# AlarmClock_Schematic.net
KiCad netlist of a schematic drawn in EAGLE
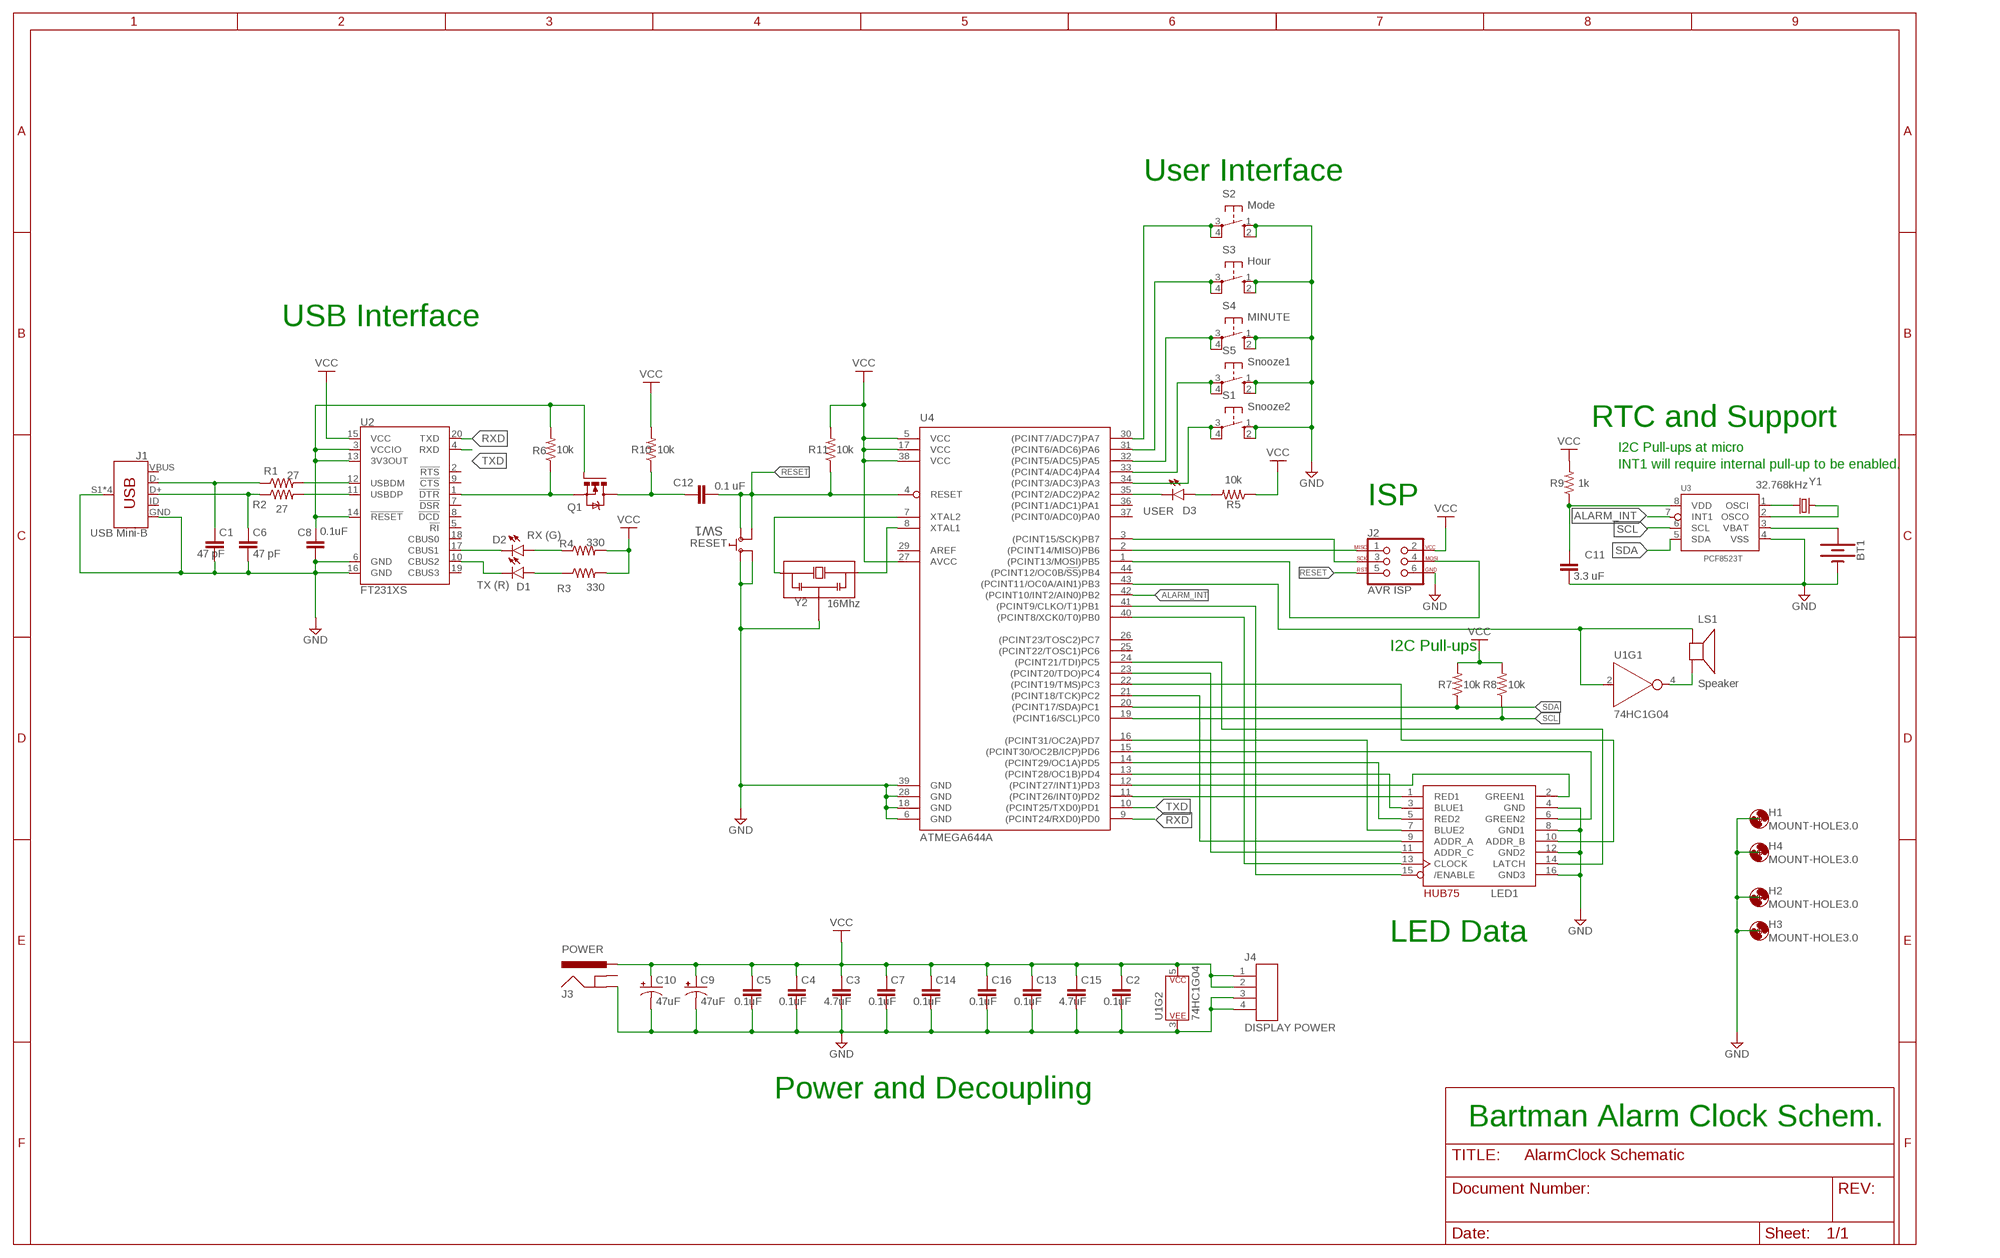
[diagram p0: schematic, sheet 1]

(export (version "E")
  (design (tool "Eeschema 10.0.6"))
  (components
    (comp (ref "BT1")
      (value "BATTERY-20MM_SMD_4LEGS")
      (footprint "eagle-import:BATTCON_20MM_4LEGS")
      (libsource (lib "eagle-import") (part "BATTERY-20MM_SMD_4LEGS"))
    )
    (comp (ref "C1")
      (value "47 pF")
      (footprint "eagle-import:CAPC2012X110")
      (libsource (lib "eagle-import") (part "CCHIP-0805(2012-METRIC)_"))
    )
    (comp (ref "C2")
      (value "0.1uF")
      (footprint "eagle-import:CAPC2012X110")
      (libsource (lib "eagle-import") (part "CCHIP-0805(2012-METRIC)_"))
    )
    (comp (ref "C3")
      (value "4.7uF")
      (footprint "eagle-import:CAPC2012X110")
      (libsource (lib "eagle-import") (part "CCHIP-0805(2012-METRIC)_"))
    )
    (comp (ref "C4")
      (value "0.1uF")
      (footprint "eagle-import:CAPC2012X110")
      (libsource (lib "eagle-import") (part "CCHIP-0805(2012-METRIC)_"))
    )
    (comp (ref "C5")
      (value "0.1uF")
      (footprint "eagle-import:CAPC2012X110")
      (libsource (lib "eagle-import") (part "CCHIP-0805(2012-METRIC)_"))
    )
    (comp (ref "C6")
      (value "47 pF")
      (footprint "eagle-import:CAPC2012X110")
      (libsource (lib "eagle-import") (part "CCHIP-0805(2012-METRIC)_"))
    )
    (comp (ref "C7")
      (value "0.1uF")
      (footprint "eagle-import:CAPC2012X110")
      (libsource (lib "eagle-import") (part "CCHIP-0805(2012-METRIC)_"))
    )
    (comp (ref "C8")
      (value "0.1uF")
      (footprint "eagle-import:CAPC2012X110")
      (libsource (lib "eagle-import") (part "CCHIP-0805(2012-METRIC)_"))
    )
    (comp (ref "C9")
      (value "47uF")
      (footprint "eagle-import:PANASONIC_D")
      (libsource (lib "eagle-import") (part "47UF-POLAR-PANASONIC_D-35V-20%"))
    )
    (comp (ref "C10")
      (value "47uF")
      (footprint "eagle-import:PANASONIC_D")
      (libsource (lib "eagle-import") (part "47UF-POLAR-PANASONIC_D-35V-20%"))
    )
    (comp (ref "C11")
      (value "3.3 uF")
      (footprint "eagle-import:CAPC2012X110")
      (libsource (lib "eagle-import") (part "CCHIP-0805(2012-METRIC)_"))
    )
    (comp (ref "C12")
      (value "0.1 uF")
      (footprint "eagle-import:CAPC2012X110")
      (libsource (lib "eagle-import") (part "CCHIP-0805(2012-METRIC)_"))
    )
    (comp (ref "C13")
      (value "0.1uF")
      (footprint "eagle-import:CAPC2012X110")
      (libsource (lib "eagle-import") (part "CCHIP-0805(2012-METRIC)_"))
    )
    (comp (ref "C14")
      (value "0.1uF")
      (footprint "eagle-import:CAPC2012X110")
      (libsource (lib "eagle-import") (part "CCHIP-0805(2012-METRIC)_"))
    )
    (comp (ref "C15")
      (value "4.7uF")
      (footprint "eagle-import:CAPC2012X110")
      (libsource (lib "eagle-import") (part "CCHIP-0805(2012-METRIC)_"))
    )
    (comp (ref "C16")
      (value "0.1uF")
      (footprint "eagle-import:CAPC2012X110")
      (libsource (lib "eagle-import") (part "CCHIP-0805(2012-METRIC)_"))
    )
    (comp (ref "D1")
      (value "TX (R)")
      (footprint "eagle-import:LEDC2012X110N_R")
      (fields (field (name "COLOR") "RED"))
      (libsource (lib "eagle-import") (part "LED_CHIPRED-2012"))
    )
    (comp (ref "D2")
      (value "RX (G)")
      (footprint "eagle-import:LEDC2012X110N_G")
      (fields (field (name "COLOR") "Green") (field (name "COLOR_1") "RX (G)"))
      (libsource (lib "eagle-import") (part "LED_CHIPGREEN-2012"))
    )
    (comp (ref "D3")
      (value "USER")
      (footprint "eagle-import:LEDC2012X110N_R")
      (fields (field (name "COLOR") "RED"))
      (libsource (lib "eagle-import") (part "LED_CHIPRED-2012"))
    )
    (comp (ref "H1")
      (value "MOUNT-HOLE3.0")
      (footprint "eagle-import:3,0")
      (libsource (lib "eagle-import") (part "MOUNT-HOLE3.0"))
    )
    (comp (ref "H2")
      (value "MOUNT-HOLE3.0")
      (footprint "eagle-import:3,0")
      (libsource (lib "eagle-import") (part "MOUNT-HOLE3.0"))
    )
    (comp (ref "H3")
      (value "MOUNT-HOLE3.0")
      (footprint "eagle-import:3,0")
      (libsource (lib "eagle-import") (part "MOUNT-HOLE3.0"))
    )
    (comp (ref "H4")
      (value "MOUNT-HOLE3.0")
      (footprint "eagle-import:3,0")
      (libsource (lib "eagle-import") (part "MOUNT-HOLE3.0"))
    )
    (comp (ref "J1")
      (value "USB Mini-B")
      (footprint "eagle-import:USB-MINIB")
      (libsource (lib "eagle-import") (part "USB_MINI-B_SMT"))
    )
    (comp (ref "J2")
      (value "AVR ISP")
      (footprint "eagle-import:2X3")
      (libsource (lib "eagle-import") (part "AVR_SPI_PROG_3X2PTH"))
    )
    (comp (ref "J3")
      (value "POWER")
      (footprint "eagle-import:POWER_JACK_PTH_BREAD")
      (libsource (lib "eagle-import") (part "POWER_JACKPTH_BREAD"))
    )
    (comp (ref "J4")
      (value "DISPLAY POWER")
      (footprint "eagle-import:JST_B4P-VH(LF)(SN)")
      (fields (field (name "MANUFACTURER") "JST Sales"))
      (libsource (lib "eagle-import") (part "B4P-VH(LF)(SN)"))
    )
    (comp (ref "LED1")
      (value "HUB75MATRIX")
      (footprint "eagle-import:2X08-IDC")
      (libsource (lib "eagle-import") (part "HUB75MATRIX"))
    )
    (comp (ref "LS1")
      (value "Speaker")
      (footprint "eagle-import:XDCR_CPT-1625-80-SMT-TR")
      (fields
        (field (name "DIGI-KEY_PART_NUMBER") "102-CPT-1625-80-SMT-CT-ND")
        (field (name "MF") "CUI Devices")
        (field (name "MP") "CPT-1625-80-SMT-TR")
      )
      (libsource (lib "eagle-import") (part "CPT-1625-80-SMT-TR"))
    )
    (comp (ref "Q1")
      (value "BSS123")
      (footprint "eagle-import:SOT23")
      (fields (field (name "MANUFACTURER") "ON Semiconductor") (field (name "MPN") "BSS123L"))
      (libsource (lib "eagle-import") (part "NMOSFET_-SOT23BSS123"))
    )
    (comp (ref "R1")
      (value "27")
      (footprint "eagle-import:RESC2012X65")
      (libsource (lib "eagle-import") (part "R-USCHIP-0805(2012-METRIC)_"))
    )
    (comp (ref "R2")
      (value "27")
      (footprint "eagle-import:RESC2012X65")
      (libsource (lib "eagle-import") (part "R-USCHIP-0805(2012-METRIC)_"))
    )
    (comp (ref "R3")
      (value "330")
      (footprint "eagle-import:RESC2012X65")
      (libsource (lib "eagle-import") (part "R-USCHIP-0805(2012-METRIC)_"))
    )
    (comp (ref "R4")
      (value "330")
      (footprint "eagle-import:RESC2012X65")
      (libsource (lib "eagle-import") (part "R-USCHIP-0805(2012-METRIC)_"))
    )
    (comp (ref "R5")
      (value "10k")
      (footprint "eagle-import:RESC2012X65")
      (libsource (lib "eagle-import") (part "R-USCHIP-0805(2012-METRIC)_"))
    )
    (comp (ref "R6")
      (value "10k")
      (footprint "eagle-import:RESC2012X65")
      (libsource (lib "eagle-import") (part "R-USCHIP-0805(2012-METRIC)_"))
    )
    (comp (ref "R7")
      (value "10k")
      (footprint "eagle-import:RESC2012X65")
      (libsource (lib "eagle-import") (part "R-USCHIP-0805(2012-METRIC)_"))
    )
    (comp (ref "R8")
      (value "10k")
      (footprint "eagle-import:RESC2012X65")
      (libsource (lib "eagle-import") (part "R-USCHIP-0805(2012-METRIC)_"))
    )
    (comp (ref "R9")
      (value "1k")
      (footprint "eagle-import:RESC2012X65")
      (libsource (lib "eagle-import") (part "R-USCHIP-0805(2012-METRIC)_"))
    )
    (comp (ref "R10")
      (value "10k")
      (footprint "eagle-import:RESC2012X65")
      (libsource (lib "eagle-import") (part "R-USCHIP-0805(2012-METRIC)_"))
    )
    (comp (ref "R11")
      (value "10k")
      (footprint "eagle-import:RESC2012X65")
      (libsource (lib "eagle-import") (part "R-USCHIP-0805(2012-METRIC)_"))
    )
    (comp (ref "S1")
      (value "Snooze2")
      (footprint "eagle-import:B3F-10XX")
      (fields
        (field (name "DIGI-KEY_PART_NUMBER") "39-B3F-1052-G-ND")
        (field (name "MF") "Omron")
        (field (name "MP") "B3F-1052")
      )
      (libsource (lib "eagle-import") (part "B3F-1052"))
    )
    (comp (ref "S2")
      (value "Mode")
      (footprint "eagle-import:B3F-10XX")
      (fields
        (field (name "DIGI-KEY_PART_NUMBER") "39-B3F-1052-G-ND")
        (field (name "MF") "Omron")
        (field (name "MP") "B3F-1052")
      )
      (libsource (lib "eagle-import") (part "B3F-1052"))
    )
    (comp (ref "S3")
      (value "Hour")
      (footprint "eagle-import:B3F-10XX")
      (fields
        (field (name "DIGI-KEY_PART_NUMBER") "39-B3F-1052-G-ND")
        (field (name "MF") "Omron")
        (field (name "MP") "B3F-1052")
      )
      (libsource (lib "eagle-import") (part "B3F-1052"))
    )
    (comp (ref "S4")
      (value "MINUTE")
      (footprint "eagle-import:B3F-10XX")
      (fields
        (field (name "DIGI-KEY_PART_NUMBER") "39-B3F-1052-G-ND")
        (field (name "MF") "Omron")
        (field (name "MP") "B3F-1052")
      )
      (libsource (lib "eagle-import") (part "B3F-1052"))
    )
    (comp (ref "S5")
      (value "Snooze1")
      (footprint "eagle-import:B3F-10XX")
      (fields
        (field (name "DIGI-KEY_PART_NUMBER") "39-B3F-1052-G-ND")
        (field (name "MF") "Omron")
        (field (name "MP") "B3F-1052")
      )
      (libsource (lib "eagle-import") (part "B3F-1052"))
    )
    (comp (ref "SW1")
      (value "FSM2JSMAA")
      (footprint "eagle-import:SWITCH_FSM2JSMAA")
      (fields (field (name "RESET") "RESET"))
      (libsource (lib "eagle-import") (part "FSM2JSMAA"))
    )
    (comp (ref "U1")
      (value "74HC1G04")
      (footprint "eagle-import:SOT353")
      (libsource (lib "eagle-import") (part "741G04HC"))
    )
    (comp (ref "U2")
      (value "FT231XS")
      (footprint "eagle-import:SSOP20_L")
      (libsource (lib "eagle-import") (part "FT231XS"))
    )
    (comp (ref "U3")
      (value "PCF8523T")
      (footprint "eagle-import:SOT96-1")
      (libsource (lib "eagle-import") (part "PCF8523T"))
    )
    (comp (ref "U4")
      (value "ATMEGA644A")
      (footprint "eagle-import:TQFP44")
      (fields (field (name "MPN") "ATMEGA644PV-10AU"))
      (libsource (lib "eagle-import") (part "ATMEGA644A"))
    )
    (comp (ref "Y1")
      (value "32.768kHz")
      (footprint "eagle-import:CRYSTAL-SMD-MC-146")
      (libsource (lib "eagle-import") (part "CRYSTAL-32.768KHZSMD-MC146"))
    )
    (comp (ref "Y2")
      (value "16Mhz")
      (footprint "eagle-import:CSTNE_3SMD")
      (fields (field (name "FREQUENCY") "16Mhz"))
      (libsource (lib "eagle-import") (part "CSTNE16M0V530000R0"))
    )
  )
  (nets
    (net (code "1") (name "/VBUS") (class "Default")
      (node (ref "J1") (pin "VBUS") (pinfunction "VBUS_VBUS") (pintype "power_in"))
    )
    (net (code "2") (name "ALARM_INT") (class "Default")
      (node (ref "U3") (pin "7") (pinfunction "INT1_7") (pintype "output"))
      (node (ref "U4") (pin "42") (pinfunction "(PCINT10/INT2/AIN0)PB2_42") (pintype "bidirectional"))
    )
    (net (code "3") (name "GND") (class "Default")
      (node (ref "BT1") (pin "NEGATIVE") (pinfunction "-_NEGATIVE") (pintype "power_in"))
      (node (ref "C1") (pin "2") (pinfunction "2_2") (pintype "passive"))
      (node (ref "C10") (pin "-") (pinfunction "-_-") (pintype "passive"))
      (node (ref "C11") (pin "2") (pinfunction "2_2") (pintype "passive"))
      (node (ref "C13") (pin "2") (pinfunction "2_2") (pintype "passive"))
      (node (ref "C14") (pin "2") (pinfunction "2_2") (pintype "passive"))
      (node (ref "C15") (pin "2") (pinfunction "2_2") (pintype "passive"))
      (node (ref "C16") (pin "2") (pinfunction "2_2") (pintype "passive"))
      (node (ref "C2") (pin "2") (pinfunction "2_2") (pintype "passive"))
      (node (ref "C3") (pin "2") (pinfunction "2_2") (pintype "passive"))
      (node (ref "C4") (pin "2") (pinfunction "2_2") (pintype "passive"))
      (node (ref "C5") (pin "2") (pinfunction "2_2") (pintype "passive"))
      (node (ref "C6") (pin "2") (pinfunction "2_2") (pintype "passive"))
      (node (ref "C7") (pin "2") (pinfunction "2_2") (pintype "passive"))
      (node (ref "C8") (pin "2") (pinfunction "2_2") (pintype "passive"))
      (node (ref "C9") (pin "-") (pinfunction "-_-") (pintype "passive"))
      (node (ref "J1") (pin "GND") (pinfunction "GND_GND") (pintype "power_in"))
      (node (ref "J1") (pin "S1") (pinfunction "SHIELD_S1") (pintype "bidirectional"))
      (node (ref "J1") (pin "S2") (pinfunction "SHIELD_S2") (pintype "bidirectional"))
      (node (ref "J1") (pin "S3") (pinfunction "SHIELD_S3") (pintype "bidirectional"))
      (node (ref "J1") (pin "S4") (pinfunction "SHIELD_S4") (pintype "bidirectional"))
      (node (ref "J2") (pin "6") (pinfunction "6_6") (pintype "passive"))
      (node (ref "J3") (pin "GND") (pinfunction "GND_GND") (pintype "bidirectional"))
      (node (ref "J4") (pin "3") (pinfunction "3_3") (pintype "passive"))
      (node (ref "J4") (pin "4") (pinfunction "4_4") (pintype "passive"))
      (node (ref "LED1") (pin "12") (pinfunction "GND2_12") (pintype "power_in"))
      (node (ref "LED1") (pin "16") (pinfunction "GND3_16") (pintype "power_in"))
      (node (ref "LED1") (pin "4") (pinfunction "GND_4") (pintype "power_in"))
      (node (ref "LED1") (pin "8") (pinfunction "GND1_8") (pintype "power_in"))
      (node (ref "S1") (pin "1") (pinfunction "S_1") (pintype "passive"))
      (node (ref "S1") (pin "2") (pinfunction "S1_2") (pintype "passive"))
      (node (ref "S2") (pin "1") (pinfunction "S_1") (pintype "passive"))
      (node (ref "S2") (pin "2") (pinfunction "S1_2") (pintype "passive"))
      (node (ref "S3") (pin "1") (pinfunction "S_1") (pintype "passive"))
      (node (ref "S3") (pin "2") (pinfunction "S1_2") (pintype "passive"))
      (node (ref "S4") (pin "1") (pinfunction "S_1") (pintype "passive"))
      (node (ref "S4") (pin "2") (pinfunction "S1_2") (pintype "passive"))
      (node (ref "S5") (pin "1") (pinfunction "S_1") (pintype "passive"))
      (node (ref "S5") (pin "2") (pinfunction "S1_2") (pintype "passive"))
      (node (ref "SW1") (pin "1") (pinfunction "1_1") (pintype "passive"))
      (node (ref "SW1") (pin "2") (pinfunction "2_2") (pintype "passive"))
      (node (ref "U1") (pin "3") (pinfunction "P$V-_3") (pintype "bidirectional"))
      (node (ref "U2") (pin "16") (pinfunction "GND_16") (pintype "bidirectional"))
      (node (ref "U2") (pin "6") (pinfunction "GND_6") (pintype "bidirectional"))
      (node (ref "U3") (pin "4") (pinfunction "VSS_4") (pintype "power_in"))
      (node (ref "U4") (pin "18") (pinfunction "GND_18") (pintype "power_in"))
      (node (ref "U4") (pin "28") (pinfunction "GND_28") (pintype "power_in"))
      (node (ref "U4") (pin "39") (pinfunction "GND_39") (pintype "power_in"))
      (node (ref "U4") (pin "6") (pinfunction "GND_6") (pintype "power_in"))
      (node (ref "Y2") (pin "2") (pinfunction "2_2") (pintype "bidirectional"))
    )
    (net (code "4") (name "Net-(C1-Pad1)") (class "Default")
      (node (ref "C1") (pin "1") (pinfunction "1_1") (pintype "passive"))
      (node (ref "J1") (pin "D-") (pinfunction "D-_D-") (pintype "bidirectional"))
      (node (ref "R1") (pin "1") (pinfunction "1_1") (pintype "passive"))
    )
    (net (code "5") (name "Net-(C6-Pad1)") (class "Default")
      (node (ref "C6") (pin "1") (pinfunction "1_1") (pintype "passive"))
      (node (ref "J1") (pin "D+") (pinfunction "D+_D+") (pintype "bidirectional"))
      (node (ref "R2") (pin "1") (pinfunction "1_1") (pintype "passive"))
    )
    (net (code "6") (name "Net-(D1-A)") (class "Default")
      (node (ref "D1") (pin "2") (pinfunction "A_2") (pintype "passive"))
      (node (ref "R3") (pin "1") (pinfunction "1_1") (pintype "passive"))
    )
    (net (code "7") (name "Net-(D1-C)") (class "Default")
      (node (ref "D1") (pin "1") (pinfunction "C_1") (pintype "passive"))
      (node (ref "U2") (pin "10") (pinfunction "CBUS2_10") (pintype "bidirectional"))
    )
    (net (code "8") (name "Net-(D2-A)") (class "Default")
      (node (ref "D2") (pin "2") (pinfunction "A_2") (pintype "passive"))
      (node (ref "R4") (pin "1") (pinfunction "1_1") (pintype "passive"))
    )
    (net (code "9") (name "Net-(D2-C)") (class "Default")
      (node (ref "D2") (pin "1") (pinfunction "C_1") (pintype "passive"))
      (node (ref "U2") (pin "17") (pinfunction "CBUS1_17") (pintype "bidirectional"))
    )
    (net (code "10") (name "Net-(D3-A)") (class "Default")
      (node (ref "D3") (pin "2") (pinfunction "A_2") (pintype "passive"))
      (node (ref "R5") (pin "2") (pinfunction "2_2") (pintype "passive"))
    )
    (net (code "11") (name "Net-(D3-C)") (class "Default")
      (node (ref "D3") (pin "1") (pinfunction "C_1") (pintype "passive"))
      (node (ref "U4") (pin "35") (pinfunction "(PCINT2/ADC2)PA2_35") (pintype "bidirectional"))
    )
    (net (code "12") (name "Net-(LED1-ADDR_A)") (class "Default")
      (node (ref "LED1") (pin "9") (pinfunction "ADDR_A_9") (pintype "input"))
      (node (ref "U4") (pin "21") (pinfunction "(PCINT18/TCK)PC2_21") (pintype "output"))
    )
    (net (code "13") (name "Net-(LED1-ADDR_B)") (class "Default")
      (node (ref "LED1") (pin "10") (pinfunction "ADDR_B_10") (pintype "input"))
      (node (ref "U4") (pin "22") (pinfunction "(PCINT19/TMS)PC3_22") (pintype "output"))
    )
    (net (code "14") (name "Net-(LED1-ADDR_C)") (class "Default")
      (node (ref "LED1") (pin "11") (pinfunction "ADDR_C_11") (pintype "input"))
      (node (ref "U4") (pin "23") (pinfunction "(PCINT20/TDO)PC4_23") (pintype "output"))
    )
    (net (code "15") (name "Net-(LED1-BLUE1)") (class "Default")
      (node (ref "LED1") (pin "3") (pinfunction "BLUE1_3") (pintype "input"))
      (node (ref "U4") (pin "13") (pinfunction "(PCINT28/OC1B)PD4_13") (pintype "bidirectional"))
    )
    (net (code "16") (name "Net-(LED1-BLUE2)") (class "Default")
      (node (ref "LED1") (pin "7") (pinfunction "BLUE2_7") (pintype "input"))
      (node (ref "U4") (pin "16") (pinfunction "(PCINT31/OC2A)PD7_16") (pintype "bidirectional"))
    )
    (net (code "17") (name "Net-(LED1-CLOCK)") (class "Default")
      (node (ref "LED1") (pin "13") (pinfunction "CLOCK_13") (pintype "input"))
      (node (ref "U4") (pin "40") (pinfunction "(PCINT8/XCK0/T0)PB0_40") (pintype "bidirectional"))
    )
    (net (code "18") (name "Net-(LED1-GREEN1)") (class "Default")
      (node (ref "LED1") (pin "2") (pinfunction "GREEN1_2") (pintype "input"))
      (node (ref "U4") (pin "12") (pinfunction "(PCINT27/INT1)PD3_12") (pintype "bidirectional"))
    )
    (net (code "19") (name "Net-(LED1-GREEN2)") (class "Default")
      (node (ref "LED1") (pin "6") (pinfunction "GREEN2_6") (pintype "input"))
      (node (ref "U4") (pin "15") (pinfunction "(PCINT30/OC2B/ICP)PD6_15") (pintype "bidirectional"))
    )
    (net (code "20") (name "Net-(LED1-LATCH)") (class "Default")
      (node (ref "LED1") (pin "14") (pinfunction "LATCH_14") (pintype "input"))
      (node (ref "U4") (pin "24") (pinfunction "(PCINT21/TDI)PC5_24") (pintype "output"))
    )
    (net (code "21") (name "Net-(LED1-RED1)") (class "Default")
      (node (ref "LED1") (pin "1") (pinfunction "RED1_1") (pintype "input"))
      (node (ref "U4") (pin "11") (pinfunction "(PCINT26/INT0)PD2_11") (pintype "bidirectional"))
    )
    (net (code "22") (name "Net-(LED1-RED2)") (class "Default")
      (node (ref "LED1") (pin "5") (pinfunction "RED2_5") (pintype "input"))
      (node (ref "U4") (pin "14") (pinfunction "(PCINT29/OC1A)PD5_14") (pintype "bidirectional"))
    )
    (net (code "23") (name "Net-(LED1-{slash}ENABLE)") (class "Default")
      (node (ref "LED1") (pin "15") (pinfunction "/ENABLE_15") (pintype "input"))
      (node (ref "U4") (pin "41") (pinfunction "(PCINT9/CLKO/T1)PB1_41") (pintype "bidirectional"))
    )
    (net (code "24") (name "Net-(Q1-D)") (class "Default")
      (node (ref "C12") (pin "1") (pinfunction "1_1") (pintype "passive"))
      (node (ref "Q1") (pin "3") (pinfunction "D_3") (pintype "passive"))
      (node (ref "R10") (pin "1") (pinfunction "1_1") (pintype "passive"))
    )
    (net (code "25") (name "Net-(Q1-G)") (class "Default")
      (node (ref "C8") (pin "1") (pinfunction "1_1") (pintype "passive"))
      (node (ref "Q1") (pin "1") (pinfunction "G_1") (pintype "passive"))
      (node (ref "R6") (pin "2") (pinfunction "2_2") (pintype "passive"))
      (node (ref "U2") (pin "13") (pinfunction "3V3OUT_13") (pintype "bidirectional"))
      (node (ref "U2") (pin "14") (pinfunction "~{RESET}_14") (pintype "bidirectional"))
      (node (ref "U2") (pin "3") (pinfunction "VCCIO_3") (pintype "bidirectional"))
    )
    (net (code "26") (name "Net-(Q1-S)") (class "Default")
      (node (ref "Q1") (pin "2") (pinfunction "S_2") (pintype "passive"))
      (node (ref "R6") (pin "1") (pinfunction "1_1") (pintype "passive"))
      (node (ref "U2") (pin "1") (pinfunction "~{DTR}_1") (pintype "bidirectional"))
    )
    (net (code "27") (name "Net-(S1-P)") (class "Default")
      (node (ref "S1") (pin "3") (pinfunction "P_3") (pintype "passive"))
      (node (ref "S1") (pin "4") (pinfunction "P1_4") (pintype "passive"))
      (node (ref "U4") (pin "34") (pinfunction "(PCINT3/ADC3)PA3_34") (pintype "bidirectional"))
    )
    (net (code "28") (name "Net-(S2-P)") (class "Default")
      (node (ref "S2") (pin "3") (pinfunction "P_3") (pintype "passive"))
      (node (ref "S2") (pin "4") (pinfunction "P1_4") (pintype "passive"))
      (node (ref "U4") (pin "30") (pinfunction "(PCINT7/ADC7)PA7_30") (pintype "bidirectional"))
    )
    (net (code "29") (name "Net-(S3-P)") (class "Default")
      (node (ref "S3") (pin "3") (pinfunction "P_3") (pintype "passive"))
      (node (ref "S3") (pin "4") (pinfunction "P1_4") (pintype "passive"))
      (node (ref "U4") (pin "31") (pinfunction "(PCINT6/ADC6)PA6_31") (pintype "bidirectional"))
    )
    (net (code "30") (name "Net-(S4-P)") (class "Default")
      (node (ref "S4") (pin "3") (pinfunction "P_3") (pintype "passive"))
      (node (ref "S4") (pin "4") (pinfunction "P1_4") (pintype "passive"))
      (node (ref "U4") (pin "32") (pinfunction "(PCINT5/ADC5)PA5_32") (pintype "bidirectional"))
    )
    (net (code "31") (name "Net-(S5-P)") (class "Default")
      (node (ref "S5") (pin "3") (pinfunction "P_3") (pintype "passive"))
      (node (ref "S5") (pin "4") (pinfunction "P1_4") (pintype "passive"))
      (node (ref "U4") (pin "33") (pinfunction "(PCINT4/ADC4)PA4_33") (pintype "bidirectional"))
    )
    (net (code "32") (name "Net-(U1A-A)") (class "Default")
      (node (ref "LS1") (pin "P") (pinfunction "P_P") (pintype "passive"))
      (node (ref "U1") (pin "2") (pinfunction "A_2") (pintype "bidirectional"))
      (node (ref "U4") (pin "43") (pinfunction "(PCINT11/OC0A/AIN1)PB3_43") (pintype "bidirectional"))
    )
    (net (code "33") (name "Net-(U1A-Y)") (class "Default")
      (node (ref "LS1") (pin "N") (pinfunction "N_N") (pintype "passive"))
      (node (ref "U1") (pin "4") (pinfunction "Y_4") (pintype "bidirectional"))
    )
    (net (code "34") (name "Net-(U2-USBDM)") (class "Default")
      (node (ref "R1") (pin "2") (pinfunction "2_2") (pintype "passive"))
      (node (ref "U2") (pin "12") (pinfunction "USBDM_12") (pintype "bidirectional"))
    )
    (net (code "35") (name "Net-(U2-USBDP)") (class "Default")
      (node (ref "R2") (pin "2") (pinfunction "2_2") (pintype "passive"))
      (node (ref "U2") (pin "11") (pinfunction "USBDP_11") (pintype "bidirectional"))
    )
    (net (code "36") (name "Net-(U3-OSCI)") (class "Default")
      (node (ref "U3") (pin "1") (pinfunction "OSCI_1") (pintype "passive"))
      (node (ref "Y1") (pin "P$1") (pinfunction "2_P$1") (pintype "passive"))
    )
    (net (code "37") (name "Net-(U3-OSCO)") (class "Default")
      (node (ref "U3") (pin "2") (pinfunction "OSCO_2") (pintype "passive"))
      (node (ref "Y1") (pin "P$2") (pinfunction "1_P$2") (pintype "passive"))
    )
    (net (code "38") (name "Net-(U3-VBAT)") (class "Default")
      (node (ref "BT1") (pin "POSITIVE@1") (pinfunction "+_POSITIVE@1") (pintype "power_in"))
      (node (ref "BT1") (pin "POSITIVE@2") (pinfunction "+_POSITIVE@2") (pintype "power_in"))
      (node (ref "BT1") (pin "POSITIVE@3") (pinfunction "+_POSITIVE@3") (pintype "power_in"))
      (node (ref "BT1") (pin "POSITIVE@4") (pinfunction "+_POSITIVE@4") (pintype "power_in"))
      (node (ref "U3") (pin "3") (pinfunction "VBAT_3") (pintype "power_in"))
    )
    (net (code "39") (name "Net-(U3-VDD)") (class "Default")
      (node (ref "C11") (pin "1") (pinfunction "1_1") (pintype "passive"))
      (node (ref "R9") (pin "1") (pinfunction "1_1") (pintype "passive"))
      (node (ref "U3") (pin "8") (pinfunction "VDD_8") (pintype "power_in"))
    )
    (net (code "40") (name "Net-(U4-(PCINT13{slash}MOSI)PB5)") (class "Default")
      (node (ref "J2") (pin "4") (pinfunction "4_4") (pintype "passive"))
      (node (ref "U4") (pin "1") (pinfunction "(PCINT13/MOSI)PB5_1") (pintype "bidirectional"))
    )
    (net (code "41") (name "Net-(U4-(PCINT14{slash}MISO)PB6)") (class "Default")
      (node (ref "J2") (pin "1") (pinfunction "1_1") (pintype "passive"))
      (node (ref "U4") (pin "2") (pinfunction "(PCINT14/MISO)PB6_2") (pintype "bidirectional"))
    )
    (net (code "42") (name "Net-(U4-(PCINT15{slash}SCK)PB7)") (class "Default")
      (node (ref "J2") (pin "3") (pinfunction "3_3") (pintype "passive"))
      (node (ref "U4") (pin "3") (pinfunction "(PCINT15/SCK)PB7_3") (pintype "bidirectional"))
    )
    (net (code "43") (name "Net-(U4-XTAL1)") (class "Default")
      (node (ref "U4") (pin "8") (pinfunction "XTAL1_8") (pintype "bidirectional"))
      (node (ref "Y2") (pin "3") (pinfunction "3_3") (pintype "bidirectional"))
    )
    (net (code "44") (name "Net-(U4-XTAL2)") (class "Default")
      (node (ref "U4") (pin "7") (pinfunction "XTAL2_7") (pintype "bidirectional"))
      (node (ref "Y2") (pin "1") (pinfunction "1_1") (pintype "bidirectional"))
    )
    (net (code "45") (name "RESET") (class "Default")
      (node (ref "C12") (pin "2") (pinfunction "2_2") (pintype "passive"))
      (node (ref "J2") (pin "5") (pinfunction "5_5") (pintype "passive"))
      (node (ref "R11") (pin "1") (pinfunction "1_1") (pintype "passive"))
      (node (ref "SW1") (pin "3") (pinfunction "3_3") (pintype "passive"))
      (node (ref "SW1") (pin "4") (pinfunction "4_4") (pintype "passive"))
      (node (ref "U4") (pin "4") (pinfunction "RESET_4") (pintype "input"))
    )
    (net (code "46") (name "RXD") (class "Default")
      (node (ref "U2") (pin "20") (pinfunction "TXD_20") (pintype "bidirectional"))
      (node (ref "U4") (pin "9") (pinfunction "(PCINT24/RXD0)PD0_9") (pintype "bidirectional"))
    )
    (net (code "47") (name "SCL") (class "Default")
      (node (ref "R8") (pin "1") (pinfunction "1_1") (pintype "passive"))
      (node (ref "U3") (pin "6") (pinfunction "SCL_6") (pintype "input"))
      (node (ref "U4") (pin "19") (pinfunction "(PCINT16/SCL)PC0_19") (pintype "output"))
    )
    (net (code "48") (name "SDA") (class "Default")
      (node (ref "R7") (pin "1") (pinfunction "1_1") (pintype "passive"))
      (node (ref "U3") (pin "5") (pinfunction "SDA_5") (pintype "bidirectional"))
      (node (ref "U4") (pin "20") (pinfunction "(PCINT17/SDA)PC1_20") (pintype "output"))
    )
    (net (code "49") (name "TXD") (class "Default")
      (node (ref "U2") (pin "4") (pinfunction "RXD_4") (pintype "bidirectional"))
      (node (ref "U4") (pin "10") (pinfunction "(PCINT25/TXD0)PD1_10") (pintype "bidirectional"))
    )
    (net (code "50") (name "VCC") (class "Default")
      (node (ref "C10") (pin "+") (pinfunction "+_+") (pintype "passive"))
      (node (ref "C13") (pin "1") (pinfunction "1_1") (pintype "passive"))
      (node (ref "C14") (pin "1") (pinfunction "1_1") (pintype "passive"))
      (node (ref "C15") (pin "1") (pinfunction "1_1") (pintype "passive"))
      (node (ref "C16") (pin "1") (pinfunction "1_1") (pintype "passive"))
      (node (ref "C2") (pin "1") (pinfunction "1_1") (pintype "passive"))
      (node (ref "C3") (pin "1") (pinfunction "1_1") (pintype "passive"))
      (node (ref "C4") (pin "1") (pinfunction "1_1") (pintype "passive"))
      (node (ref "C5") (pin "1") (pinfunction "1_1") (pintype "passive"))
      (node (ref "C7") (pin "1") (pinfunction "1_1") (pintype "passive"))
      (node (ref "C9") (pin "+") (pinfunction "+_+") (pintype "passive"))
      (node (ref "J2") (pin "2") (pinfunction "2_2") (pintype "passive"))
      (node (ref "J3") (pin "PWR") (pinfunction "PWR_PWR") (pintype "bidirectional"))
      (node (ref "J4") (pin "1") (pinfunction "1_1") (pintype "passive"))
      (node (ref "J4") (pin "2") (pinfunction "2_2") (pintype "passive"))
      (node (ref "R10") (pin "2") (pinfunction "2_2") (pintype "passive"))
      (node (ref "R11") (pin "2") (pinfunction "2_2") (pintype "passive"))
      (node (ref "R3") (pin "2") (pinfunction "2_2") (pintype "passive"))
      (node (ref "R4") (pin "2") (pinfunction "2_2") (pintype "passive"))
      (node (ref "R5") (pin "1") (pinfunction "1_1") (pintype "passive"))
      (node (ref "R7") (pin "2") (pinfunction "2_2") (pintype "passive"))
      (node (ref "R8") (pin "2") (pinfunction "2_2") (pintype "passive"))
      (node (ref "R9") (pin "2") (pinfunction "2_2") (pintype "passive"))
      (node (ref "U1") (pin "5") (pinfunction "P$V+_5") (pintype "bidirectional"))
      (node (ref "U2") (pin "15") (pinfunction "VCC_15") (pintype "bidirectional"))
      (node (ref "U4") (pin "17") (pinfunction "VCC_17") (pintype "power_in"))
      (node (ref "U4") (pin "27") (pinfunction "AVCC_27") (pintype "power_in"))
      (node (ref "U4") (pin "38") (pinfunction "VCC_38") (pintype "power_in"))
      (node (ref "U4") (pin "5") (pinfunction "VCC_5") (pintype "power_in"))
    )
    (net (code "51") (name "unconnected-(J1-PadID)") (class "Default")
      (node (ref "J1") (pin "ID") (pinfunction "ID_ID") (pintype "bidirectional"))
    )
    (net (code "52") (name "unconnected-(J3-PadGNDBREAK)") (class "Default")
      (node (ref "J3") (pin "GNDBREAK") (pinfunction "GNDBREAK_GNDBREAK") (pintype "bidirectional"))
    )
    (net (code "53") (name "unconnected-(U2-CBUS0-Pad18)") (class "Default")
      (node (ref "U2") (pin "18") (pinfunction "CBUS0_18") (pintype "bidirectional"))
    )
    (net (code "54") (name "unconnected-(U2-CBUS3-Pad19)") (class "Default")
      (node (ref "U2") (pin "19") (pinfunction "CBUS3_19") (pintype "bidirectional"))
    )
    (net (code "55") (name "unconnected-(U2-~{CTS}-Pad9)") (class "Default")
      (node (ref "U2") (pin "9") (pinfunction "~{CTS}_9") (pintype "bidirectional"))
    )
    (net (code "56") (name "unconnected-(U2-~{DCD}-Pad8)") (class "Default")
      (node (ref "U2") (pin "8") (pinfunction "~{DCD}_8") (pintype "bidirectional"))
    )
    (net (code "57") (name "unconnected-(U2-~{DSR}-Pad7)") (class "Default")
      (node (ref "U2") (pin "7") (pinfunction "~{DSR}_7") (pintype "bidirectional"))
    )
    (net (code "58") (name "unconnected-(U2-~{RI}-Pad5)") (class "Default")
      (node (ref "U2") (pin "5") (pinfunction "~{RI}_5") (pintype "bidirectional"))
    )
    (net (code "59") (name "unconnected-(U2-~{RTS}-Pad2)") (class "Default")
      (node (ref "U2") (pin "2") (pinfunction "~{RTS}_2") (pintype "bidirectional"))
    )
    (net (code "60") (name "unconnected-(U4-(PCINT0{slash}ADC0)PA0-Pad37)") (class "Default")
      (node (ref "U4") (pin "37") (pinfunction "(PCINT0/ADC0)PA0_37") (pintype "bidirectional"))
    )
    (net (code "61") (name "unconnected-(U4-(PCINT1{slash}ADC1)PA1-Pad36)") (class "Default")
      (node (ref "U4") (pin "36") (pinfunction "(PCINT1/ADC1)PA1_36") (pintype "bidirectional"))
    )
    (net (code "62") (name "unconnected-(U4-(PCINT12{slash}OC0B{slash}~{SS})PB4-Pad44)") (class "Default")
      (node (ref "U4") (pin "44") (pinfunction "(PCINT12/OC0B/~{SS})PB4_44") (pintype "bidirectional"))
    )
    (net (code "63") (name "unconnected-(U4-(PCINT22{slash}TOSC1)PC6-Pad25)") (class "Default")
      (node (ref "U4") (pin "25") (pinfunction "(PCINT22/TOSC1)PC6_25") (pintype "output"))
    )
    (net (code "64") (name "unconnected-(U4-(PCINT23{slash}TOSC2)PC7-Pad26)") (class "Default")
      (node (ref "U4") (pin "26") (pinfunction "(PCINT23/TOSC2)PC7_26") (pintype "output"))
    )
    (net (code "65") (name "unconnected-(U4-AREF-Pad29)") (class "Default")
      (node (ref "U4") (pin "29") (pinfunction "AREF_29") (pintype "passive"))
    )
  )
)
